# PCB_SCH_Left_Main.net
KiCad netlist of a schematic drawn in EasyEDA Pro
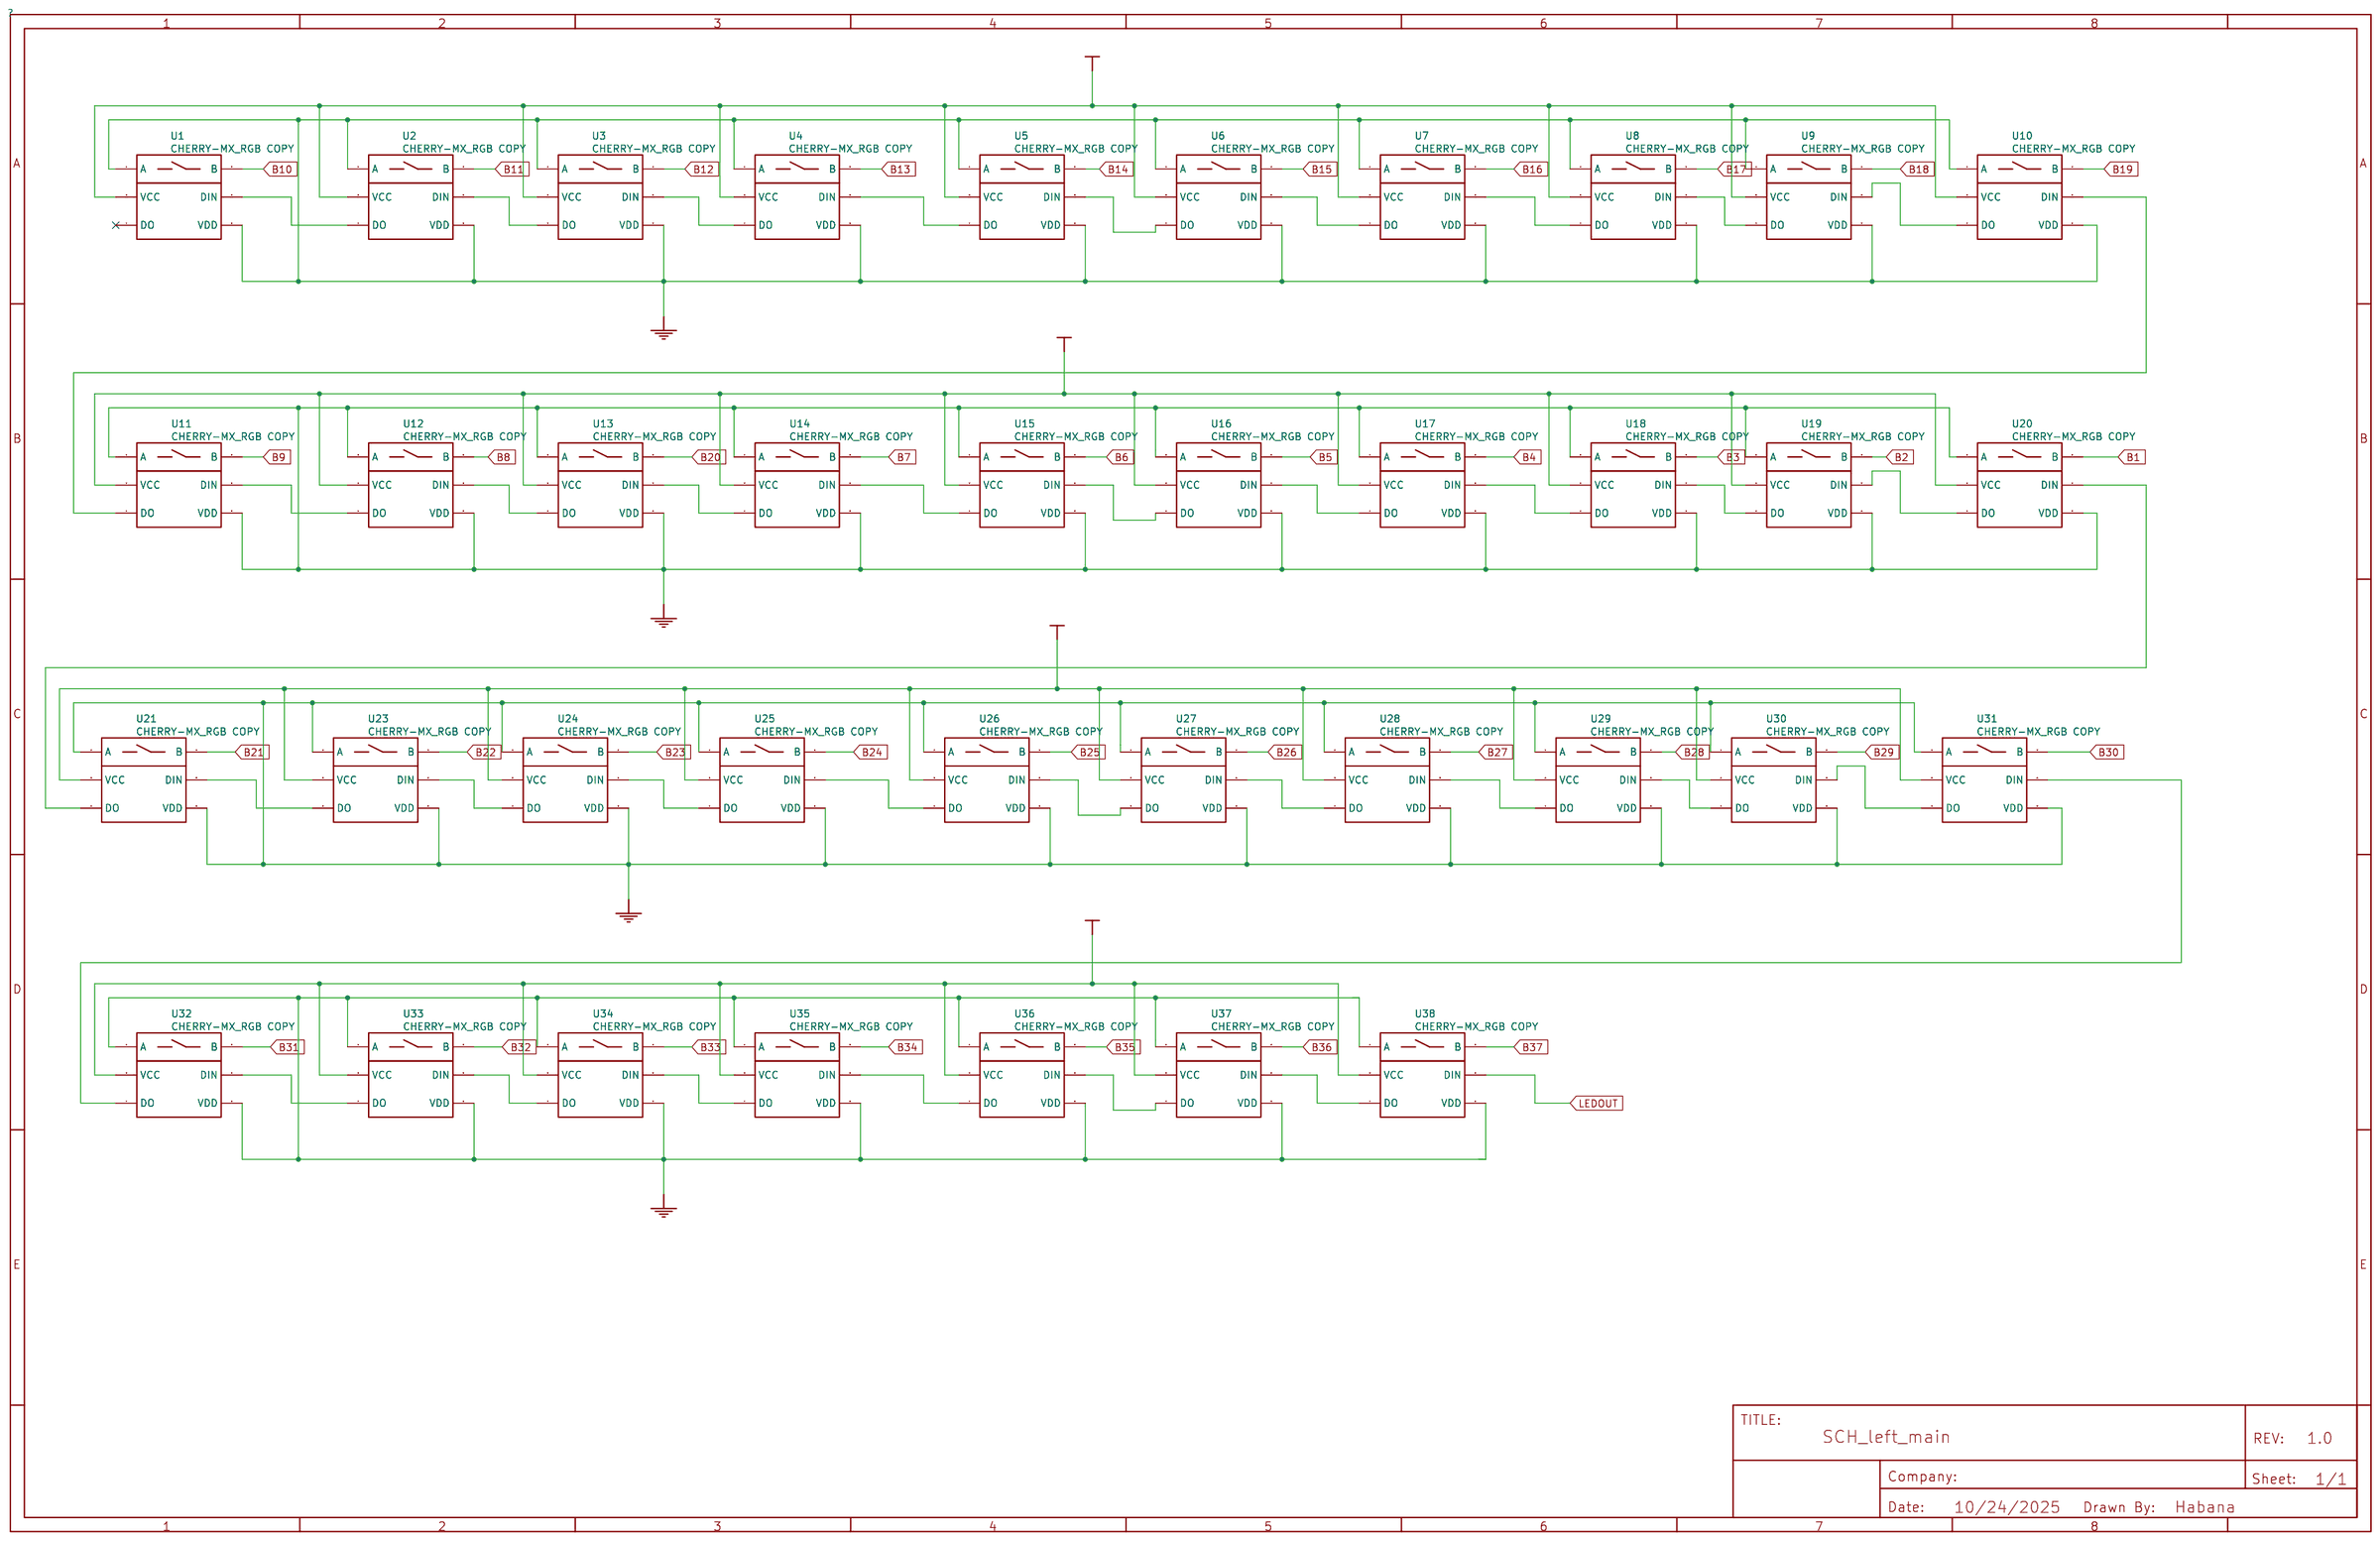
[diagram p0: led and button]
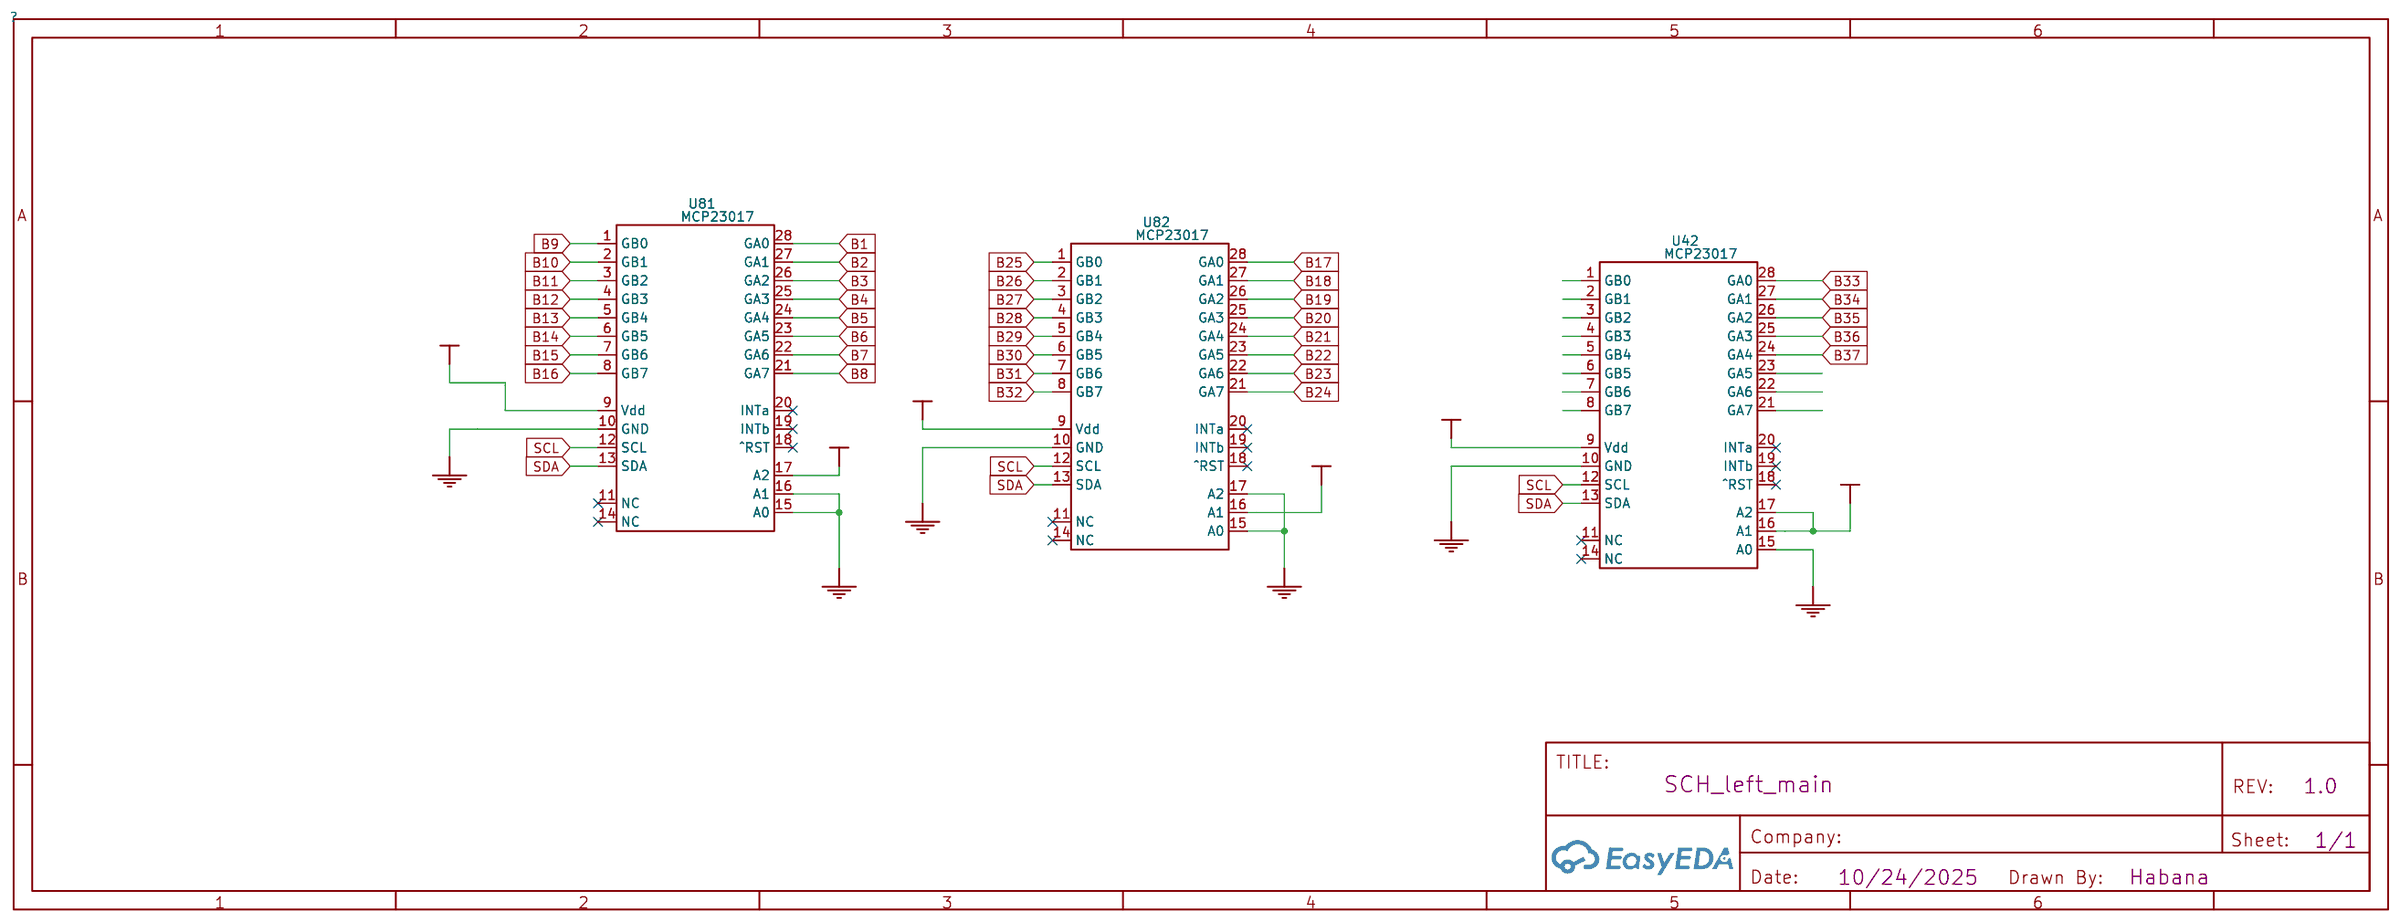
[diagram p1: drivers]
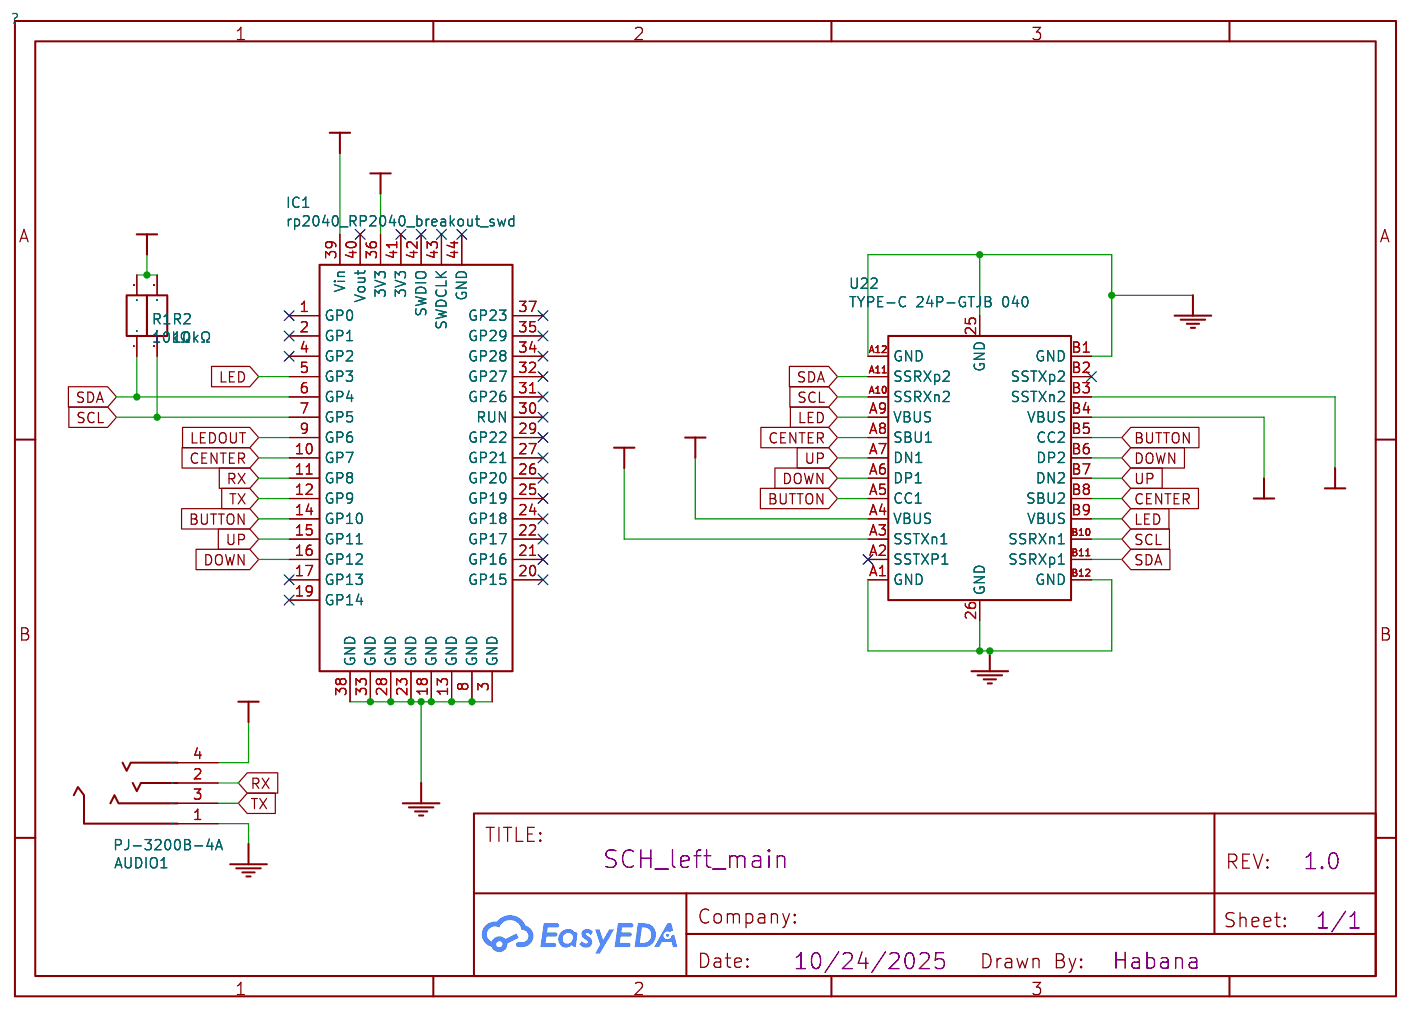
[diagram p2: microcontroller]

(export (version "E")
  (design (tool "Eeschema 10.0.6"))
  (components
    (comp (ref "U1")
      (value "CHERRY-MX_RGB COPY")
      (fields (field (name "Contributor") "unrealin01"))
      (libsource (lib "easyedapro") (part "CHERRY-MX_RGB COPY"))
    )
    (comp (ref "U2")
      (value "CHERRY-MX_RGB COPY")
      (fields (field (name "Contributor") "unrealin01"))
      (libsource (lib "easyedapro") (part "CHERRY-MX_RGB COPY"))
    )
    (comp (ref "U3")
      (value "CHERRY-MX_RGB COPY")
      (fields (field (name "Contributor") "unrealin01"))
      (libsource (lib "easyedapro") (part "CHERRY-MX_RGB COPY"))
    )
    (comp (ref "U4")
      (value "CHERRY-MX_RGB COPY")
      (fields (field (name "Contributor") "unrealin01"))
      (libsource (lib "easyedapro") (part "CHERRY-MX_RGB COPY"))
    )
    (comp (ref "U5")
      (value "CHERRY-MX_RGB COPY")
      (fields (field (name "Contributor") "unrealin01"))
      (libsource (lib "easyedapro") (part "CHERRY-MX_RGB COPY"))
    )
    (comp (ref "U6")
      (value "CHERRY-MX_RGB COPY")
      (fields (field (name "Contributor") "unrealin01"))
      (libsource (lib "easyedapro") (part "CHERRY-MX_RGB COPY"))
    )
    (comp (ref "U7")
      (value "CHERRY-MX_RGB COPY")
      (fields (field (name "Contributor") "unrealin01"))
      (libsource (lib "easyedapro") (part "CHERRY-MX_RGB COPY"))
    )
    (comp (ref "U8")
      (value "CHERRY-MX_RGB COPY")
      (fields (field (name "Contributor") "unrealin01"))
      (libsource (lib "easyedapro") (part "CHERRY-MX_RGB COPY"))
    )
    (comp (ref "U9")
      (value "CHERRY-MX_RGB COPY")
      (fields (field (name "Contributor") "unrealin01"))
      (libsource (lib "easyedapro") (part "CHERRY-MX_RGB COPY"))
    )
    (comp (ref "U10")
      (value "CHERRY-MX_RGB COPY")
      (fields (field (name "Contributor") "unrealin01"))
      (libsource (lib "easyedapro") (part "CHERRY-MX_RGB COPY"))
    )
    (comp (ref "U11")
      (value "CHERRY-MX_RGB COPY")
      (fields (field (name "Contributor") "unrealin01"))
      (libsource (lib "easyedapro") (part "CHERRY-MX_RGB COPY"))
    )
    (comp (ref "U12")
      (value "CHERRY-MX_RGB COPY")
      (fields (field (name "Contributor") "unrealin01"))
      (libsource (lib "easyedapro") (part "CHERRY-MX_RGB COPY"))
    )
    (comp (ref "U13")
      (value "CHERRY-MX_RGB COPY")
      (fields (field (name "Contributor") "unrealin01"))
      (libsource (lib "easyedapro") (part "CHERRY-MX_RGB COPY"))
    )
    (comp (ref "U14")
      (value "CHERRY-MX_RGB COPY")
      (fields (field (name "Contributor") "unrealin01"))
      (libsource (lib "easyedapro") (part "CHERRY-MX_RGB COPY"))
    )
    (comp (ref "U15")
      (value "CHERRY-MX_RGB COPY")
      (fields (field (name "Contributor") "unrealin01"))
      (libsource (lib "easyedapro") (part "CHERRY-MX_RGB COPY"))
    )
    (comp (ref "U16")
      (value "CHERRY-MX_RGB COPY")
      (fields (field (name "Contributor") "unrealin01"))
      (libsource (lib "easyedapro") (part "CHERRY-MX_RGB COPY"))
    )
    (comp (ref "U17")
      (value "CHERRY-MX_RGB COPY")
      (fields (field (name "Contributor") "unrealin01"))
      (libsource (lib "easyedapro") (part "CHERRY-MX_RGB COPY"))
    )
    (comp (ref "U18")
      (value "CHERRY-MX_RGB COPY")
      (fields (field (name "Contributor") "unrealin01"))
      (libsource (lib "easyedapro") (part "CHERRY-MX_RGB COPY"))
    )
    (comp (ref "U19")
      (value "CHERRY-MX_RGB COPY")
      (fields (field (name "Contributor") "unrealin01"))
      (libsource (lib "easyedapro") (part "CHERRY-MX_RGB COPY"))
    )
    (comp (ref "U20")
      (value "CHERRY-MX_RGB COPY")
      (fields (field (name "Contributor") "unrealin01"))
      (libsource (lib "easyedapro") (part "CHERRY-MX_RGB COPY"))
    )
    (comp (ref "U21")
      (value "CHERRY-MX_RGB COPY")
      (fields (field (name "Contributor") "unrealin01"))
      (libsource (lib "easyedapro") (part "CHERRY-MX_RGB COPY"))
    )
    (comp (ref "U23")
      (value "CHERRY-MX_RGB COPY")
      (fields (field (name "Contributor") "unrealin01"))
      (libsource (lib "easyedapro") (part "CHERRY-MX_RGB COPY"))
    )
    (comp (ref "U24")
      (value "CHERRY-MX_RGB COPY")
      (fields (field (name "Contributor") "unrealin01"))
      (libsource (lib "easyedapro") (part "CHERRY-MX_RGB COPY"))
    )
    (comp (ref "U25")
      (value "CHERRY-MX_RGB COPY")
      (fields (field (name "Contributor") "unrealin01"))
      (libsource (lib "easyedapro") (part "CHERRY-MX_RGB COPY"))
    )
    (comp (ref "U26")
      (value "CHERRY-MX_RGB COPY")
      (fields (field (name "Contributor") "unrealin01"))
      (libsource (lib "easyedapro") (part "CHERRY-MX_RGB COPY"))
    )
    (comp (ref "U27")
      (value "CHERRY-MX_RGB COPY")
      (fields (field (name "Contributor") "unrealin01"))
      (libsource (lib "easyedapro") (part "CHERRY-MX_RGB COPY"))
    )
    (comp (ref "U28")
      (value "CHERRY-MX_RGB COPY")
      (fields (field (name "Contributor") "unrealin01"))
      (libsource (lib "easyedapro") (part "CHERRY-MX_RGB COPY"))
    )
    (comp (ref "U29")
      (value "CHERRY-MX_RGB COPY")
      (fields (field (name "Contributor") "unrealin01"))
      (libsource (lib "easyedapro") (part "CHERRY-MX_RGB COPY"))
    )
    (comp (ref "U30")
      (value "CHERRY-MX_RGB COPY")
      (fields (field (name "Contributor") "unrealin01"))
      (libsource (lib "easyedapro") (part "CHERRY-MX_RGB COPY"))
    )
    (comp (ref "U31")
      (value "CHERRY-MX_RGB COPY")
      (fields (field (name "Contributor") "unrealin01"))
      (libsource (lib "easyedapro") (part "CHERRY-MX_RGB COPY"))
    )
    (comp (ref "U32")
      (value "CHERRY-MX_RGB COPY")
      (fields (field (name "Contributor") "unrealin01"))
      (libsource (lib "easyedapro") (part "CHERRY-MX_RGB COPY"))
    )
    (comp (ref "U33")
      (value "CHERRY-MX_RGB COPY")
      (fields (field (name "Contributor") "unrealin01"))
      (libsource (lib "easyedapro") (part "CHERRY-MX_RGB COPY"))
    )
    (comp (ref "U34")
      (value "CHERRY-MX_RGB COPY")
      (fields (field (name "Contributor") "unrealin01"))
      (libsource (lib "easyedapro") (part "CHERRY-MX_RGB COPY"))
    )
    (comp (ref "U35")
      (value "CHERRY-MX_RGB COPY")
      (fields (field (name "Contributor") "unrealin01"))
      (libsource (lib "easyedapro") (part "CHERRY-MX_RGB COPY"))
    )
    (comp (ref "U36")
      (value "CHERRY-MX_RGB COPY")
      (fields (field (name "Contributor") "unrealin01"))
      (libsource (lib "easyedapro") (part "CHERRY-MX_RGB COPY"))
    )
    (comp (ref "U37")
      (value "CHERRY-MX_RGB COPY")
      (fields (field (name "Contributor") "unrealin01"))
      (libsource (lib "easyedapro") (part "CHERRY-MX_RGB COPY"))
    )
    (comp (ref "U38")
      (value "CHERRY-MX_RGB COPY")
      (fields (field (name "Contributor") "unrealin01"))
      (libsource (lib "easyedapro") (part "CHERRY-MX_RGB COPY"))
    )
    (comp (ref "U42")
      (value "MCP23017")
      (fields (field (name "Contributor") "tsvstar"))
      (libsource (lib "easyedapro") (part "MCP23017"))
    )
    (comp (ref "U81")
      (value "MCP23017")
      (fields (field (name "Contributor") "tsvstar"))
      (libsource (lib "easyedapro") (part "MCP23017"))
    )
    (comp (ref "U82")
      (value "MCP23017")
      (fields (field (name "Contributor") "tsvstar"))
      (libsource (lib "easyedapro") (part "MCP23017"))
    )
    (comp (ref "AUDIO1")
      (value "PJ-3200B-4A")
      (footprint "easyedapro:AUDIO-TH_PJ-3200B-4A")
      (fields (field (name "Manufacturer") "韩国韩荣") (field (name "Contributor") "LCSC"))
      (libsource (lib "easyedapro") (part "PJ-3200B-4A"))
    )
    (comp (ref "IC1")
      (value "rp2040_RP2040_breakout_swd")
      (fields (field (name "Contributor") "rataweb"))
      (libsource (lib "easyedapro") (part "rp2040_RP2040_breakout_swd"))
    )
    (comp (ref "R1")
      (value "10kΩ")
      (footprint "easyedapro:R1206")
      (fields
        (field (name "Manufacturer Part") "RCT0610KJLF")
        (field (name "Manufacturer") "HKR(香港电阻)")
        (field (name "Contributor") "LCSC")
      )
      (libsource (lib "easyedapro") (part "10kΩ"))
    )
    (comp (ref "R2")
      (value "10kΩ")
      (footprint "easyedapro:R1206")
      (fields
        (field (name "Manufacturer Part") "RCT0610KJLF")
        (field (name "Manufacturer") "HKR(香港电阻)")
        (field (name "Contributor") "LCSC")
      )
      (libsource (lib "easyedapro") (part "10kΩ"))
    )
    (comp (ref "U22")
      (value "TYPE-C 24P-GTJB 040")
      (footprint "easyedapro:USB-C-SMD_TYPE-C-24P-GTJB-040")
      (fields (field (name "Manufacturer") "SHOU HAN(首韩)") (field (name "Contributor") "lcsc"))
      (libsource (lib "easyedapro") (part "TYPE-C 24P-GTJB 040"))
    )
  )
  (nets
    (net (code "1") (name "+5V") (class "Default")
      (node (ref "IC1") (pin "39") (pinfunction "Vin_39") (pintype "unspecified"))
      (node (ref "R1") (pin "2") (pinfunction "2_2") (pintype "unspecified"))
      (node (ref "R2") (pin "2") (pinfunction "2_2") (pintype "unspecified"))
      (node (ref "U1") (pin "3") (pinfunction "VCC_3") (pintype "unspecified"))
      (node (ref "U10") (pin "3") (pinfunction "VCC_3") (pintype "unspecified"))
      (node (ref "U11") (pin "3") (pinfunction "VCC_3") (pintype "unspecified"))
      (node (ref "U12") (pin "3") (pinfunction "VCC_3") (pintype "unspecified"))
      (node (ref "U13") (pin "3") (pinfunction "VCC_3") (pintype "unspecified"))
      (node (ref "U14") (pin "3") (pinfunction "VCC_3") (pintype "unspecified"))
      (node (ref "U15") (pin "3") (pinfunction "VCC_3") (pintype "unspecified"))
      (node (ref "U16") (pin "3") (pinfunction "VCC_3") (pintype "unspecified"))
      (node (ref "U17") (pin "3") (pinfunction "VCC_3") (pintype "unspecified"))
      (node (ref "U18") (pin "3") (pinfunction "VCC_3") (pintype "unspecified"))
      (node (ref "U19") (pin "3") (pinfunction "VCC_3") (pintype "unspecified"))
      (node (ref "U2") (pin "3") (pinfunction "VCC_3") (pintype "unspecified"))
      (node (ref "U20") (pin "3") (pinfunction "VCC_3") (pintype "unspecified"))
      (node (ref "U21") (pin "3") (pinfunction "VCC_3") (pintype "unspecified"))
      (node (ref "U22") (pin "A4") (pinfunction "VBUS_A4") (pintype "unspecified"))
      (node (ref "U22") (pin "B4") (pinfunction "VBUS_B4") (pintype "unspecified"))
      (node (ref "U23") (pin "3") (pinfunction "VCC_3") (pintype "unspecified"))
      (node (ref "U24") (pin "3") (pinfunction "VCC_3") (pintype "unspecified"))
      (node (ref "U25") (pin "3") (pinfunction "VCC_3") (pintype "unspecified"))
      (node (ref "U26") (pin "3") (pinfunction "VCC_3") (pintype "unspecified"))
      (node (ref "U27") (pin "3") (pinfunction "VCC_3") (pintype "unspecified"))
      (node (ref "U28") (pin "3") (pinfunction "VCC_3") (pintype "unspecified"))
      (node (ref "U29") (pin "3") (pinfunction "VCC_3") (pintype "unspecified"))
      (node (ref "U3") (pin "3") (pinfunction "VCC_3") (pintype "unspecified"))
      (node (ref "U30") (pin "3") (pinfunction "VCC_3") (pintype "unspecified"))
      (node (ref "U31") (pin "3") (pinfunction "VCC_3") (pintype "unspecified"))
      (node (ref "U32") (pin "3") (pinfunction "VCC_3") (pintype "unspecified"))
      (node (ref "U33") (pin "3") (pinfunction "VCC_3") (pintype "unspecified"))
      (node (ref "U34") (pin "3") (pinfunction "VCC_3") (pintype "unspecified"))
      (node (ref "U35") (pin "3") (pinfunction "VCC_3") (pintype "unspecified"))
      (node (ref "U36") (pin "3") (pinfunction "VCC_3") (pintype "unspecified"))
      (node (ref "U37") (pin "3") (pinfunction "VCC_3") (pintype "unspecified"))
      (node (ref "U38") (pin "3") (pinfunction "VCC_3") (pintype "unspecified"))
      (node (ref "U4") (pin "3") (pinfunction "VCC_3") (pintype "unspecified"))
      (node (ref "U5") (pin "3") (pinfunction "VCC_3") (pintype "unspecified"))
      (node (ref "U6") (pin "3") (pinfunction "VCC_3") (pintype "unspecified"))
      (node (ref "U7") (pin "3") (pinfunction "VCC_3") (pintype "unspecified"))
      (node (ref "U8") (pin "3") (pinfunction "VCC_3") (pintype "unspecified"))
      (node (ref "U9") (pin "3") (pinfunction "VCC_3") (pintype "unspecified"))
    )
    (net (code "2") (name "B1") (class "Default")
      (node (ref "U20") (pin "2") (pinfunction "B_2") (pintype "unspecified"))
      (node (ref "U81") (pin "28") (pinfunction "GA0_28") (pintype "unspecified"))
    )
    (net (code "3") (name "B2") (class "Default")
      (node (ref "U19") (pin "2") (pinfunction "B_2") (pintype "unspecified"))
      (node (ref "U81") (pin "27") (pinfunction "GA1_27") (pintype "unspecified"))
    )
    (net (code "4") (name "B3") (class "Default")
      (node (ref "U18") (pin "2") (pinfunction "B_2") (pintype "unspecified"))
      (node (ref "U81") (pin "26") (pinfunction "GA2_26") (pintype "unspecified"))
    )
    (net (code "5") (name "B4") (class "Default")
      (node (ref "U17") (pin "2") (pinfunction "B_2") (pintype "unspecified"))
      (node (ref "U81") (pin "25") (pinfunction "GA3_25") (pintype "unspecified"))
    )
    (net (code "6") (name "B5") (class "Default")
      (node (ref "U16") (pin "2") (pinfunction "B_2") (pintype "unspecified"))
      (node (ref "U81") (pin "24") (pinfunction "GA4_24") (pintype "unspecified"))
    )
    (net (code "7") (name "B6") (class "Default")
      (node (ref "U15") (pin "2") (pinfunction "B_2") (pintype "unspecified"))
      (node (ref "U81") (pin "23") (pinfunction "GA5_23") (pintype "unspecified"))
    )
    (net (code "8") (name "B7") (class "Default")
      (node (ref "U14") (pin "2") (pinfunction "B_2") (pintype "unspecified"))
      (node (ref "U81") (pin "22") (pinfunction "GA6_22") (pintype "unspecified"))
    )
    (net (code "9") (name "B8") (class "Default")
      (node (ref "U12") (pin "2") (pinfunction "B_2") (pintype "unspecified"))
      (node (ref "U81") (pin "21") (pinfunction "GA7_21") (pintype "unspecified"))
    )
    (net (code "10") (name "B9") (class "Default")
      (node (ref "U11") (pin "2") (pinfunction "B_2") (pintype "unspecified"))
      (node (ref "U81") (pin "1") (pinfunction "GB0_1") (pintype "unspecified"))
    )
    (net (code "11") (name "B10") (class "Default")
      (node (ref "U1") (pin "2") (pinfunction "B_2") (pintype "unspecified"))
      (node (ref "U81") (pin "2") (pinfunction "GB1_2") (pintype "unspecified"))
    )
    (net (code "12") (name "B11") (class "Default")
      (node (ref "U2") (pin "2") (pinfunction "B_2") (pintype "unspecified"))
      (node (ref "U81") (pin "3") (pinfunction "GB2_3") (pintype "unspecified"))
    )
    (net (code "13") (name "B12") (class "Default")
      (node (ref "U3") (pin "2") (pinfunction "B_2") (pintype "unspecified"))
      (node (ref "U81") (pin "4") (pinfunction "GB3_4") (pintype "unspecified"))
    )
    (net (code "14") (name "B13") (class "Default")
      (node (ref "U4") (pin "2") (pinfunction "B_2") (pintype "unspecified"))
      (node (ref "U81") (pin "5") (pinfunction "GB4_5") (pintype "unspecified"))
    )
    (net (code "15") (name "B14") (class "Default")
      (node (ref "U5") (pin "2") (pinfunction "B_2") (pintype "unspecified"))
      (node (ref "U81") (pin "6") (pinfunction "GB5_6") (pintype "unspecified"))
    )
    (net (code "16") (name "B15") (class "Default")
      (node (ref "U6") (pin "2") (pinfunction "B_2") (pintype "unspecified"))
      (node (ref "U81") (pin "7") (pinfunction "GB6_7") (pintype "unspecified"))
    )
    (net (code "17") (name "B16") (class "Default")
      (node (ref "U7") (pin "2") (pinfunction "B_2") (pintype "unspecified"))
      (node (ref "U81") (pin "8") (pinfunction "GB7_8") (pintype "unspecified"))
    )
    (net (code "18") (name "B17") (class "Default")
      (node (ref "U8") (pin "2") (pinfunction "B_2") (pintype "unspecified"))
      (node (ref "U82") (pin "28") (pinfunction "GA0_28") (pintype "unspecified"))
    )
    (net (code "19") (name "B18") (class "Default")
      (node (ref "U82") (pin "27") (pinfunction "GA1_27") (pintype "unspecified"))
      (node (ref "U9") (pin "2") (pinfunction "B_2") (pintype "unspecified"))
    )
    (net (code "20") (name "B19") (class "Default")
      (node (ref "U10") (pin "2") (pinfunction "B_2") (pintype "unspecified"))
      (node (ref "U82") (pin "26") (pinfunction "GA2_26") (pintype "unspecified"))
    )
    (net (code "21") (name "B20") (class "Default")
      (node (ref "U13") (pin "2") (pinfunction "B_2") (pintype "unspecified"))
      (node (ref "U82") (pin "25") (pinfunction "GA3_25") (pintype "unspecified"))
    )
    (net (code "22") (name "B21") (class "Default")
      (node (ref "U21") (pin "2") (pinfunction "B_2") (pintype "unspecified"))
      (node (ref "U82") (pin "24") (pinfunction "GA4_24") (pintype "unspecified"))
    )
    (net (code "23") (name "B22") (class "Default")
      (node (ref "U23") (pin "2") (pinfunction "B_2") (pintype "unspecified"))
      (node (ref "U82") (pin "23") (pinfunction "GA5_23") (pintype "unspecified"))
    )
    (net (code "24") (name "B23") (class "Default")
      (node (ref "U24") (pin "2") (pinfunction "B_2") (pintype "unspecified"))
      (node (ref "U82") (pin "22") (pinfunction "GA6_22") (pintype "unspecified"))
    )
    (net (code "25") (name "B24") (class "Default")
      (node (ref "U25") (pin "2") (pinfunction "B_2") (pintype "unspecified"))
      (node (ref "U82") (pin "21") (pinfunction "GA7_21") (pintype "unspecified"))
    )
    (net (code "26") (name "B25") (class "Default")
      (node (ref "U26") (pin "2") (pinfunction "B_2") (pintype "unspecified"))
      (node (ref "U82") (pin "1") (pinfunction "GB0_1") (pintype "unspecified"))
    )
    (net (code "27") (name "B26") (class "Default")
      (node (ref "U27") (pin "2") (pinfunction "B_2") (pintype "unspecified"))
      (node (ref "U82") (pin "2") (pinfunction "GB1_2") (pintype "unspecified"))
    )
    (net (code "28") (name "B27") (class "Default")
      (node (ref "U28") (pin "2") (pinfunction "B_2") (pintype "unspecified"))
      (node (ref "U82") (pin "3") (pinfunction "GB2_3") (pintype "unspecified"))
    )
    (net (code "29") (name "B28") (class "Default")
      (node (ref "U29") (pin "2") (pinfunction "B_2") (pintype "unspecified"))
      (node (ref "U82") (pin "4") (pinfunction "GB3_4") (pintype "unspecified"))
    )
    (net (code "30") (name "B29") (class "Default")
      (node (ref "U30") (pin "2") (pinfunction "B_2") (pintype "unspecified"))
      (node (ref "U82") (pin "5") (pinfunction "GB4_5") (pintype "unspecified"))
    )
    (net (code "31") (name "B30") (class "Default")
      (node (ref "U31") (pin "2") (pinfunction "B_2") (pintype "unspecified"))
      (node (ref "U82") (pin "6") (pinfunction "GB5_6") (pintype "unspecified"))
    )
    (net (code "32") (name "B31") (class "Default")
      (node (ref "U32") (pin "2") (pinfunction "B_2") (pintype "unspecified"))
      (node (ref "U82") (pin "7") (pinfunction "GB6_7") (pintype "unspecified"))
    )
    (net (code "33") (name "B32") (class "Default")
      (node (ref "U33") (pin "2") (pinfunction "B_2") (pintype "unspecified"))
      (node (ref "U82") (pin "8") (pinfunction "GB7_8") (pintype "unspecified"))
    )
    (net (code "34") (name "B33") (class "Default")
      (node (ref "U34") (pin "2") (pinfunction "B_2") (pintype "unspecified"))
      (node (ref "U42") (pin "28") (pinfunction "GA0_28") (pintype "unspecified"))
    )
    (net (code "35") (name "B34") (class "Default")
      (node (ref "U35") (pin "2") (pinfunction "B_2") (pintype "unspecified"))
      (node (ref "U42") (pin "27") (pinfunction "GA1_27") (pintype "unspecified"))
    )
    (net (code "36") (name "B35") (class "Default")
      (node (ref "U36") (pin "2") (pinfunction "B_2") (pintype "unspecified"))
      (node (ref "U42") (pin "26") (pinfunction "GA2_26") (pintype "unspecified"))
    )
    (net (code "37") (name "B36") (class "Default")
      (node (ref "U37") (pin "2") (pinfunction "B_2") (pintype "unspecified"))
      (node (ref "U42") (pin "25") (pinfunction "GA3_25") (pintype "unspecified"))
    )
    (net (code "38") (name "B37") (class "Default")
      (node (ref "U38") (pin "2") (pinfunction "B_2") (pintype "unspecified"))
      (node (ref "U42") (pin "24") (pinfunction "GA4_24") (pintype "unspecified"))
    )
    (net (code "39") (name "BUTTON") (class "Default")
      (node (ref "IC1") (pin "14") (pinfunction "GP10_14") (pintype "unspecified"))
      (node (ref "U22") (pin "A5") (pinfunction "CC1_A5") (pintype "unspecified"))
      (node (ref "U22") (pin "B5") (pinfunction "CC2_B5") (pintype "unspecified"))
    )
    (net (code "40") (name "CENTER") (class "Default")
      (node (ref "IC1") (pin "10") (pinfunction "GP7_10") (pintype "unspecified"))
      (node (ref "U22") (pin "A8") (pinfunction "SBU1_A8") (pintype "unspecified"))
      (node (ref "U22") (pin "B8") (pinfunction "SBU2_B8") (pintype "unspecified"))
    )
    (net (code "41") (name "DOWN") (class "Default")
      (node (ref "IC1") (pin "16") (pinfunction "GP12_16") (pintype "unspecified"))
      (node (ref "U22") (pin "A6") (pinfunction "DP1_A6") (pintype "unspecified"))
      (node (ref "U22") (pin "B6") (pinfunction "DP2_B6") (pintype "unspecified"))
    )
    (net (code "42") (name "GND") (class "Default")
      (node (ref "AUDIO1") (pin "1") (pinfunction "1_1") (pintype "unspecified"))
      (node (ref "IC1") (pin "13") (pinfunction "GND_13") (pintype "unspecified"))
      (node (ref "IC1") (pin "18") (pinfunction "GND_18") (pintype "unspecified"))
      (node (ref "IC1") (pin "23") (pinfunction "GND_23") (pintype "unspecified"))
      (node (ref "IC1") (pin "28") (pinfunction "GND_28") (pintype "unspecified"))
      (node (ref "IC1") (pin "3") (pinfunction "GND_3") (pintype "unspecified"))
      (node (ref "IC1") (pin "33") (pinfunction "GND_33") (pintype "unspecified"))
      (node (ref "IC1") (pin "38") (pinfunction "GND_38") (pintype "unspecified"))
      (node (ref "IC1") (pin "8") (pinfunction "GND_8") (pintype "unspecified"))
      (node (ref "U1") (pin "1") (pinfunction "A_1") (pintype "unspecified"))
      (node (ref "U1") (pin "5") (pinfunction "VDD_5") (pintype "unspecified"))
      (node (ref "U10") (pin "1") (pinfunction "A_1") (pintype "unspecified"))
      (node (ref "U10") (pin "5") (pinfunction "VDD_5") (pintype "unspecified"))
      (node (ref "U11") (pin "1") (pinfunction "A_1") (pintype "unspecified"))
      (node (ref "U11") (pin "5") (pinfunction "VDD_5") (pintype "unspecified"))
      (node (ref "U12") (pin "1") (pinfunction "A_1") (pintype "unspecified"))
      (node (ref "U12") (pin "5") (pinfunction "VDD_5") (pintype "unspecified"))
      (node (ref "U13") (pin "1") (pinfunction "A_1") (pintype "unspecified"))
      (node (ref "U13") (pin "5") (pinfunction "VDD_5") (pintype "unspecified"))
      (node (ref "U14") (pin "1") (pinfunction "A_1") (pintype "unspecified"))
      (node (ref "U14") (pin "5") (pinfunction "VDD_5") (pintype "unspecified"))
      (node (ref "U15") (pin "1") (pinfunction "A_1") (pintype "unspecified"))
      (node (ref "U15") (pin "5") (pinfunction "VDD_5") (pintype "unspecified"))
      (node (ref "U16") (pin "1") (pinfunction "A_1") (pintype "unspecified"))
      (node (ref "U16") (pin "5") (pinfunction "VDD_5") (pintype "unspecified"))
      (node (ref "U17") (pin "1") (pinfunction "A_1") (pintype "unspecified"))
      (node (ref "U17") (pin "5") (pinfunction "VDD_5") (pintype "unspecified"))
      (node (ref "U18") (pin "1") (pinfunction "A_1") (pintype "unspecified"))
      (node (ref "U18") (pin "5") (pinfunction "VDD_5") (pintype "unspecified"))
      (node (ref "U19") (pin "1") (pinfunction "A_1") (pintype "unspecified"))
      (node (ref "U19") (pin "5") (pinfunction "VDD_5") (pintype "unspecified"))
      (node (ref "U2") (pin "1") (pinfunction "A_1") (pintype "unspecified"))
      (node (ref "U2") (pin "5") (pinfunction "VDD_5") (pintype "unspecified"))
      (node (ref "U20") (pin "1") (pinfunction "A_1") (pintype "unspecified"))
      (node (ref "U20") (pin "5") (pinfunction "VDD_5") (pintype "unspecified"))
      (node (ref "U21") (pin "1") (pinfunction "A_1") (pintype "unspecified"))
      (node (ref "U21") (pin "5") (pinfunction "VDD_5") (pintype "unspecified"))
      (node (ref "U22") (pin "25") (pinfunction "GND_25") (pintype "unspecified"))
      (node (ref "U22") (pin "26") (pinfunction "GND_26") (pintype "unspecified"))
      (node (ref "U22") (pin "A1") (pinfunction "GND_A1") (pintype "unspecified"))
      (node (ref "U22") (pin "A12") (pinfunction "GND_A12") (pintype "unspecified"))
      (node (ref "U22") (pin "B1") (pinfunction "GND_B1") (pintype "unspecified"))
      (node (ref "U22") (pin "B12") (pinfunction "GND_B12") (pintype "unspecified"))
      (node (ref "U23") (pin "1") (pinfunction "A_1") (pintype "unspecified"))
      (node (ref "U23") (pin "5") (pinfunction "VDD_5") (pintype "unspecified"))
      (node (ref "U24") (pin "1") (pinfunction "A_1") (pintype "unspecified"))
      (node (ref "U24") (pin "5") (pinfunction "VDD_5") (pintype "unspecified"))
      (node (ref "U25") (pin "1") (pinfunction "A_1") (pintype "unspecified"))
      (node (ref "U25") (pin "5") (pinfunction "VDD_5") (pintype "unspecified"))
      (node (ref "U26") (pin "1") (pinfunction "A_1") (pintype "unspecified"))
      (node (ref "U26") (pin "5") (pinfunction "VDD_5") (pintype "unspecified"))
      (node (ref "U27") (pin "1") (pinfunction "A_1") (pintype "unspecified"))
      (node (ref "U27") (pin "5") (pinfunction "VDD_5") (pintype "unspecified"))
      (node (ref "U28") (pin "1") (pinfunction "A_1") (pintype "unspecified"))
      (node (ref "U28") (pin "5") (pinfunction "VDD_5") (pintype "unspecified"))
      (node (ref "U29") (pin "1") (pinfunction "A_1") (pintype "unspecified"))
      (node (ref "U29") (pin "5") (pinfunction "VDD_5") (pintype "unspecified"))
      (node (ref "U3") (pin "1") (pinfunction "A_1") (pintype "unspecified"))
      (node (ref "U3") (pin "5") (pinfunction "VDD_5") (pintype "unspecified"))
      (node (ref "U30") (pin "1") (pinfunction "A_1") (pintype "unspecified"))
      (node (ref "U30") (pin "5") (pinfunction "VDD_5") (pintype "unspecified"))
      (node (ref "U31") (pin "1") (pinfunction "A_1") (pintype "unspecified"))
      (node (ref "U31") (pin "5") (pinfunction "VDD_5") (pintype "unspecified"))
      (node (ref "U32") (pin "1") (pinfunction "A_1") (pintype "unspecified"))
      (node (ref "U32") (pin "5") (pinfunction "VDD_5") (pintype "unspecified"))
      (node (ref "U33") (pin "1") (pinfunction "A_1") (pintype "unspecified"))
      (node (ref "U33") (pin "5") (pinfunction "VDD_5") (pintype "unspecified"))
      (node (ref "U34") (pin "1") (pinfunction "A_1") (pintype "unspecified"))
      (node (ref "U34") (pin "5") (pinfunction "VDD_5") (pintype "unspecified"))
      (node (ref "U35") (pin "1") (pinfunction "A_1") (pintype "unspecified"))
      (node (ref "U35") (pin "5") (pinfunction "VDD_5") (pintype "unspecified"))
      (node (ref "U36") (pin "1") (pinfunction "A_1") (pintype "unspecified"))
      (node (ref "U36") (pin "5") (pinfunction "VDD_5") (pintype "unspecified"))
      (node (ref "U37") (pin "1") (pinfunction "A_1") (pintype "unspecified"))
      (node (ref "U37") (pin "5") (pinfunction "VDD_5") (pintype "unspecified"))
      (node (ref "U38") (pin "1") (pinfunction "A_1") (pintype "unspecified"))
      (node (ref "U38") (pin "5") (pinfunction "VDD_5") (pintype "unspecified"))
      (node (ref "U4") (pin "1") (pinfunction "A_1") (pintype "unspecified"))
      (node (ref "U4") (pin "5") (pinfunction "VDD_5") (pintype "unspecified"))
      (node (ref "U42") (pin "10") (pinfunction "GND_10") (pintype "unspecified"))
      (node (ref "U42") (pin "15") (pinfunction "A0_15") (pintype "unspecified"))
      (node (ref "U5") (pin "1") (pinfunction "A_1") (pintype "unspecified"))
      (node (ref "U5") (pin "5") (pinfunction "VDD_5") (pintype "unspecified"))
      (node (ref "U6") (pin "1") (pinfunction "A_1") (pintype "unspecified"))
      (node (ref "U6") (pin "5") (pinfunction "VDD_5") (pintype "unspecified"))
      (node (ref "U7") (pin "1") (pinfunction "A_1") (pintype "unspecified"))
      (node (ref "U7") (pin "5") (pinfunction "VDD_5") (pintype "unspecified"))
      (node (ref "U8") (pin "1") (pinfunction "A_1") (pintype "unspecified"))
      (node (ref "U8") (pin "5") (pinfunction "VDD_5") (pintype "unspecified"))
      (node (ref "U81") (pin "10") (pinfunction "GND_10") (pintype "unspecified"))
      (node (ref "U81") (pin "15") (pinfunction "A0_15") (pintype "unspecified"))
      (node (ref "U81") (pin "16") (pinfunction "A1_16") (pintype "unspecified"))
      (node (ref "U82") (pin "10") (pinfunction "GND_10") (pintype "unspecified"))
      (node (ref "U82") (pin "15") (pinfunction "A0_15") (pintype "unspecified"))
      (node (ref "U82") (pin "17") (pinfunction "A2_17") (pintype "unspecified"))
      (node (ref "U9") (pin "1") (pinfunction "A_1") (pintype "unspecified"))
      (node (ref "U9") (pin "5") (pinfunction "VDD_5") (pintype "unspecified"))
    )
    (net (code "43") (name "LED") (class "Default")
      (node (ref "IC1") (pin "5") (pinfunction "GP3_5") (pintype "unspecified"))
      (node (ref "U22") (pin "A9") (pinfunction "VBUS_A9") (pintype "unspecified"))
      (node (ref "U22") (pin "B9") (pinfunction "VBUS_B9") (pintype "unspecified"))
    )
    (net (code "44") (name "LEDOUT") (class "Default")
      (node (ref "IC1") (pin "9") (pinfunction "GP6_9") (pintype "unspecified"))
      (node (ref "U38") (pin "6") (pinfunction "DIN_6") (pintype "unspecified"))
    )
    (net (code "45") (name "Net-(U1-DIN)") (class "Default")
      (node (ref "U1") (pin "6") (pinfunction "DIN_6") (pintype "unspecified"))
      (node (ref "U2") (pin "4") (pinfunction "DO_4") (pintype "unspecified"))
    )
    (net (code "46") (name "Net-(U2-DIN)") (class "Default")
      (node (ref "U2") (pin "6") (pinfunction "DIN_6") (pintype "unspecified"))
      (node (ref "U3") (pin "4") (pinfunction "DO_4") (pintype "unspecified"))
    )
    (net (code "47") (name "Net-(U3-DIN)") (class "Default")
      (node (ref "U3") (pin "6") (pinfunction "DIN_6") (pintype "unspecified"))
      (node (ref "U4") (pin "4") (pinfunction "DO_4") (pintype "unspecified"))
    )
    (net (code "48") (name "Net-(U4-DIN)") (class "Default")
      (node (ref "U4") (pin "6") (pinfunction "DIN_6") (pintype "unspecified"))
      (node (ref "U5") (pin "4") (pinfunction "DO_4") (pintype "unspecified"))
    )
    (net (code "49") (name "Net-(U5-DIN)") (class "Default")
      (node (ref "U5") (pin "6") (pinfunction "DIN_6") (pintype "unspecified"))
      (node (ref "U6") (pin "4") (pinfunction "DO_4") (pintype "unspecified"))
    )
    (net (code "50") (name "Net-(U6-DIN)") (class "Default")
      (node (ref "U6") (pin "6") (pinfunction "DIN_6") (pintype "unspecified"))
      (node (ref "U7") (pin "4") (pinfunction "DO_4") (pintype "unspecified"))
    )
    (net (code "51") (name "Net-(U7-DIN)") (class "Default")
      (node (ref "U7") (pin "6") (pinfunction "DIN_6") (pintype "unspecified"))
      (node (ref "U8") (pin "4") (pinfunction "DO_4") (pintype "unspecified"))
    )
    (net (code "52") (name "Net-(U8-DIN)") (class "Default")
      (node (ref "U8") (pin "6") (pinfunction "DIN_6") (pintype "unspecified"))
      (node (ref "U9") (pin "4") (pinfunction "DO_4") (pintype "unspecified"))
    )
    (net (code "53") (name "Net-(U10-DIN)") (class "Default")
      (node (ref "U10") (pin "6") (pinfunction "DIN_6") (pintype "unspecified"))
      (node (ref "U11") (pin "4") (pinfunction "DO_4") (pintype "unspecified"))
    )
    (net (code "54") (name "Net-(U10-DO)") (class "Default")
      (node (ref "U10") (pin "4") (pinfunction "DO_4") (pintype "unspecified"))
      (node (ref "U9") (pin "6") (pinfunction "DIN_6") (pintype "unspecified"))
    )
    (net (code "55") (name "Net-(U11-DIN)") (class "Default")
      (node (ref "U11") (pin "6") (pinfunction "DIN_6") (pintype "unspecified"))
      (node (ref "U12") (pin "4") (pinfunction "DO_4") (pintype "unspecified"))
    )
    (net (code "56") (name "Net-(U12-DIN)") (class "Default")
      (node (ref "U12") (pin "6") (pinfunction "DIN_6") (pintype "unspecified"))
      (node (ref "U13") (pin "4") (pinfunction "DO_4") (pintype "unspecified"))
    )
    (net (code "57") (name "Net-(U13-DIN)") (class "Default")
      (node (ref "U13") (pin "6") (pinfunction "DIN_6") (pintype "unspecified"))
      (node (ref "U14") (pin "4") (pinfunction "DO_4") (pintype "unspecified"))
    )
    (net (code "58") (name "Net-(U14-DIN)") (class "Default")
      (node (ref "U14") (pin "6") (pinfunction "DIN_6") (pintype "unspecified"))
      (node (ref "U15") (pin "4") (pinfunction "DO_4") (pintype "unspecified"))
    )
    (net (code "59") (name "Net-(U15-DIN)") (class "Default")
      (node (ref "U15") (pin "6") (pinfunction "DIN_6") (pintype "unspecified"))
      (node (ref "U16") (pin "4") (pinfunction "DO_4") (pintype "unspecified"))
    )
    (net (code "60") (name "Net-(U16-DIN)") (class "Default")
      (node (ref "U16") (pin "6") (pinfunction "DIN_6") (pintype "unspecified"))
      (node (ref "U17") (pin "4") (pinfunction "DO_4") (pintype "unspecified"))
    )
    (net (code "61") (name "Net-(U17-DIN)") (class "Default")
      (node (ref "U17") (pin "6") (pinfunction "DIN_6") (pintype "unspecified"))
      (node (ref "U18") (pin "4") (pinfunction "DO_4") (pintype "unspecified"))
    )
    (net (code "62") (name "Net-(U18-DIN)") (class "Default")
      (node (ref "U18") (pin "6") (pinfunction "DIN_6") (pintype "unspecified"))
      (node (ref "U19") (pin "4") (pinfunction "DO_4") (pintype "unspecified"))
    )
    (net (code "63") (name "Net-(U19-DIN)") (class "Default")
      (node (ref "U19") (pin "6") (pinfunction "DIN_6") (pintype "unspecified"))
      (node (ref "U20") (pin "4") (pinfunction "DO_4") (pintype "unspecified"))
    )
    (net (code "64") (name "Net-(U20-DIN)") (class "Default")
      (node (ref "U20") (pin "6") (pinfunction "DIN_6") (pintype "unspecified"))
      (node (ref "U21") (pin "4") (pinfunction "DO_4") (pintype "unspecified"))
    )
    (net (code "65") (name "Net-(U21-DIN)") (class "Default")
      (node (ref "U21") (pin "6") (pinfunction "DIN_6") (pintype "unspecified"))
      (node (ref "U23") (pin "4") (pinfunction "DO_4") (pintype "unspecified"))
    )
    (net (code "66") (name "Net-(U23-DIN)") (class "Default")
      (node (ref "U23") (pin "6") (pinfunction "DIN_6") (pintype "unspecified"))
      (node (ref "U24") (pin "4") (pinfunction "DO_4") (pintype "unspecified"))
    )
    (net (code "67") (name "Net-(U24-DIN)") (class "Default")
      (node (ref "U24") (pin "6") (pinfunction "DIN_6") (pintype "unspecified"))
      (node (ref "U25") (pin "4") (pinfunction "DO_4") (pintype "unspecified"))
    )
    (net (code "68") (name "Net-(U25-DIN)") (class "Default")
      (node (ref "U25") (pin "6") (pinfunction "DIN_6") (pintype "unspecified"))
      (node (ref "U26") (pin "4") (pinfunction "DO_4") (pintype "unspecified"))
    )
    (net (code "69") (name "Net-(U26-DIN)") (class "Default")
      (node (ref "U26") (pin "6") (pinfunction "DIN_6") (pintype "unspecified"))
      (node (ref "U27") (pin "4") (pinfunction "DO_4") (pintype "unspecified"))
    )
    (net (code "70") (name "Net-(U27-DIN)") (class "Default")
      (node (ref "U27") (pin "6") (pinfunction "DIN_6") (pintype "unspecified"))
      (node (ref "U28") (pin "4") (pinfunction "DO_4") (pintype "unspecified"))
    )
    (net (code "71") (name "Net-(U28-DIN)") (class "Default")
      (node (ref "U28") (pin "6") (pinfunction "DIN_6") (pintype "unspecified"))
      (node (ref "U29") (pin "4") (pinfunction "DO_4") (pintype "unspecified"))
    )
    (net (code "72") (name "Net-(U29-DIN)") (class "Default")
      (node (ref "U29") (pin "6") (pinfunction "DIN_6") (pintype "unspecified"))
      (node (ref "U30") (pin "4") (pinfunction "DO_4") (pintype "unspecified"))
    )
    (net (code "73") (name "Net-(U30-DIN)") (class "Default")
      (node (ref "U30") (pin "6") (pinfunction "DIN_6") (pintype "unspecified"))
      (node (ref "U31") (pin "4") (pinfunction "DO_4") (pintype "unspecified"))
    )
    (net (code "74") (name "Net-(U31-DIN)") (class "Default")
      (node (ref "U31") (pin "6") (pinfunction "DIN_6") (pintype "unspecified"))
      (node (ref "U32") (pin "4") (pinfunction "DO_4") (pintype "unspecified"))
    )
    (net (code "75") (name "Net-(U32-DIN)") (class "Default")
      (node (ref "U32") (pin "6") (pinfunction "DIN_6") (pintype "unspecified"))
      (node (ref "U33") (pin "4") (pinfunction "DO_4") (pintype "unspecified"))
    )
    (net (code "76") (name "Net-(U33-DIN)") (class "Default")
      (node (ref "U33") (pin "6") (pinfunction "DIN_6") (pintype "unspecified"))
      (node (ref "U34") (pin "4") (pinfunction "DO_4") (pintype "unspecified"))
    )
    (net (code "77") (name "Net-(U34-DIN)") (class "Default")
      (node (ref "U34") (pin "6") (pinfunction "DIN_6") (pintype "unspecified"))
      (node (ref "U35") (pin "4") (pinfunction "DO_4") (pintype "unspecified"))
    )
    (net (code "78") (name "Net-(U35-DIN)") (class "Default")
      (node (ref "U35") (pin "6") (pinfunction "DIN_6") (pintype "unspecified"))
      (node (ref "U36") (pin "4") (pinfunction "DO_4") (pintype "unspecified"))
    )
    (net (code "79") (name "Net-(U36-DIN)") (class "Default")
      (node (ref "U36") (pin "6") (pinfunction "DIN_6") (pintype "unspecified"))
      (node (ref "U37") (pin "4") (pinfunction "DO_4") (pintype "unspecified"))
    )
    (net (code "80") (name "Net-(U37-DIN)") (class "Default")
      (node (ref "U37") (pin "6") (pinfunction "DIN_6") (pintype "unspecified"))
      (node (ref "U38") (pin "4") (pinfunction "DO_4") (pintype "unspecified"))
    )
    (net (code "81") (name "RX") (class "Default")
      (node (ref "AUDIO1") (pin "2") (pinfunction "2_2") (pintype "unspecified"))
      (node (ref "IC1") (pin "11") (pinfunction "GP8_11") (pintype "unspecified"))
    )
    (net (code "82") (name "SCL") (class "Default")
      (node (ref "IC1") (pin "7") (pinfunction "GP5_7") (pintype "unspecified"))
      (node (ref "R2") (pin "1") (pinfunction "1_1") (pintype "unspecified"))
      (node (ref "U22") (pin "A10") (pinfunction "SSRXn2_A10") (pintype "unspecified"))
      (node (ref "U22") (pin "B10") (pinfunction "SSRXn1_B10") (pintype "unspecified"))
      (node (ref "U42") (pin "12") (pinfunction "SCL_12") (pintype "unspecified"))
      (node (ref "U81") (pin "12") (pinfunction "SCL_12") (pintype "unspecified"))
      (node (ref "U82") (pin "12") (pinfunction "SCL_12") (pintype "unspecified"))
    )
    (net (code "83") (name "SDA") (class "Default")
      (node (ref "IC1") (pin "6") (pinfunction "GP4_6") (pintype "unspecified"))
      (node (ref "R1") (pin "1") (pinfunction "1_1") (pintype "unspecified"))
      (node (ref "U22") (pin "A11") (pinfunction "SSRXp2_A11") (pintype "unspecified"))
      (node (ref "U22") (pin "B11") (pinfunction "SSRXp1_B11") (pintype "unspecified"))
      (node (ref "U42") (pin "13") (pinfunction "SDA_13") (pintype "unspecified"))
      (node (ref "U81") (pin "13") (pinfunction "SDA_13") (pintype "unspecified"))
      (node (ref "U82") (pin "13") (pinfunction "SDA_13") (pintype "unspecified"))
    )
    (net (code "84") (name "TX") (class "Default")
      (node (ref "AUDIO1") (pin "3") (pinfunction "3_3") (pintype "unspecified"))
      (node (ref "IC1") (pin "12") (pinfunction "GP9_12") (pintype "unspecified"))
    )
    (net (code "85") (name "UP") (class "Default")
      (node (ref "IC1") (pin "15") (pinfunction "GP11_15") (pintype "unspecified"))
      (node (ref "U22") (pin "A7") (pinfunction "DN1_A7") (pintype "unspecified"))
      (node (ref "U22") (pin "B7") (pinfunction "DN2_B7") (pintype "unspecified"))
    )
    (net (code "86") (name "VCC") (class "Default")
      (node (ref "AUDIO1") (pin "4") (pinfunction "4_4") (pintype "unspecified"))
      (node (ref "IC1") (pin "36") (pinfunction "3V3_36") (pintype "unspecified"))
      (node (ref "U22") (pin "A3") (pinfunction "SSTXn1_A3") (pintype "unspecified"))
      (node (ref "U22") (pin "B3") (pinfunction "SSTXn2_B3") (pintype "unspecified"))
      (node (ref "U42") (pin "16") (pinfunction "A1_16") (pintype "unspecified"))
      (node (ref "U42") (pin "17") (pinfunction "A2_17") (pintype "unspecified"))
      (node (ref "U42") (pin "9") (pinfunction "Vdd_9") (pintype "unspecified"))
      (node (ref "U81") (pin "17") (pinfunction "A2_17") (pintype "unspecified"))
      (node (ref "U81") (pin "9") (pinfunction "Vdd_9") (pintype "unspecified"))
      (node (ref "U82") (pin "16") (pinfunction "A1_16") (pintype "unspecified"))
      (node (ref "U82") (pin "9") (pinfunction "Vdd_9") (pintype "unspecified"))
    )
    (net (code "87") (name "unconnected-(IC1-3V3-Pad41)") (class "Default")
      (node (ref "IC1") (pin "41") (pinfunction "3V3_41") (pintype "unspecified+no_connect"))
    )
    (net (code "88") (name "unconnected-(IC1-GND-Pad44)") (class "Default")
      (node (ref "IC1") (pin "44") (pinfunction "GND_44") (pintype "unspecified+no_connect"))
    )
    (net (code "89") (name "unconnected-(IC1-GP0-Pad1)") (class "Default")
      (node (ref "IC1") (pin "1") (pinfunction "GP0_1") (pintype "unspecified+no_connect"))
    )
    (net (code "90") (name "unconnected-(IC1-GP1-Pad2)") (class "Default")
      (node (ref "IC1") (pin "2") (pinfunction "GP1_2") (pintype "unspecified+no_connect"))
    )
    (net (code "91") (name "unconnected-(IC1-GP2-Pad4)") (class "Default")
      (node (ref "IC1") (pin "4") (pinfunction "GP2_4") (pintype "unspecified+no_connect"))
    )
    (net (code "92") (name "unconnected-(IC1-GP13-Pad17)") (class "Default")
      (node (ref "IC1") (pin "17") (pinfunction "GP13_17") (pintype "unspecified+no_connect"))
    )
    (net (code "93") (name "unconnected-(IC1-GP14-Pad19)") (class "Default")
      (node (ref "IC1") (pin "19") (pinfunction "GP14_19") (pintype "unspecified+no_connect"))
    )
    (net (code "94") (name "unconnected-(IC1-GP15-Pad20)") (class "Default")
      (node (ref "IC1") (pin "20") (pinfunction "GP15_20") (pintype "unspecified+no_connect"))
    )
    (net (code "95") (name "unconnected-(IC1-GP16-Pad21)") (class "Default")
      (node (ref "IC1") (pin "21") (pinfunction "GP16_21") (pintype "unspecified+no_connect"))
    )
    (net (code "96") (name "unconnected-(IC1-GP17-Pad22)") (class "Default")
      (node (ref "IC1") (pin "22") (pinfunction "GP17_22") (pintype "unspecified+no_connect"))
    )
    (net (code "97") (name "unconnected-(IC1-GP18-Pad24)") (class "Default")
      (node (ref "IC1") (pin "24") (pinfunction "GP18_24") (pintype "unspecified+no_connect"))
    )
    (net (code "98") (name "unconnected-(IC1-GP19-Pad25)") (class "Default")
      (node (ref "IC1") (pin "25") (pinfunction "GP19_25") (pintype "unspecified+no_connect"))
    )
    (net (code "99") (name "unconnected-(IC1-GP20-Pad26)") (class "Default")
      (node (ref "IC1") (pin "26") (pinfunction "GP20_26") (pintype "unspecified+no_connect"))
    )
    (net (code "100") (name "unconnected-(IC1-GP21-Pad27)") (class "Default")
      (node (ref "IC1") (pin "27") (pinfunction "GP21_27") (pintype "unspecified+no_connect"))
    )
    (net (code "101") (name "unconnected-(IC1-GP22-Pad29)") (class "Default")
      (node (ref "IC1") (pin "29") (pinfunction "GP22_29") (pintype "unspecified+no_connect"))
    )
    (net (code "102") (name "unconnected-(IC1-GP23-Pad37)") (class "Default")
      (node (ref "IC1") (pin "37") (pinfunction "GP23_37") (pintype "unspecified+no_connect"))
    )
    (net (code "103") (name "unconnected-(IC1-GP26-Pad31)") (class "Default")
      (node (ref "IC1") (pin "31") (pinfunction "GP26_31") (pintype "unspecified+no_connect"))
    )
    (net (code "104") (name "unconnected-(IC1-GP27-Pad32)") (class "Default")
      (node (ref "IC1") (pin "32") (pinfunction "GP27_32") (pintype "unspecified+no_connect"))
    )
    (net (code "105") (name "unconnected-(IC1-GP28-Pad34)") (class "Default")
      (node (ref "IC1") (pin "34") (pinfunction "GP28_34") (pintype "unspecified+no_connect"))
    )
    (net (code "106") (name "unconnected-(IC1-GP29-Pad35)") (class "Default")
      (node (ref "IC1") (pin "35") (pinfunction "GP29_35") (pintype "unspecified+no_connect"))
    )
    (net (code "107") (name "unconnected-(IC1-RUN-Pad30)") (class "Default")
      (node (ref "IC1") (pin "30") (pinfunction "RUN_30") (pintype "unspecified+no_connect"))
    )
    (net (code "108") (name "unconnected-(IC1-SWDCLK-Pad43)") (class "Default")
      (node (ref "IC1") (pin "43") (pinfunction "SWDCLK_43") (pintype "unspecified+no_connect"))
    )
    (net (code "109") (name "unconnected-(IC1-SWDIO-Pad42)") (class "Default")
      (node (ref "IC1") (pin "42") (pinfunction "SWDIO_42") (pintype "unspecified+no_connect"))
    )
    (net (code "110") (name "unconnected-(IC1-Vout-Pad40)") (class "Default")
      (node (ref "IC1") (pin "40") (pinfunction "Vout_40") (pintype "unspecified+no_connect"))
    )
    (net (code "111") (name "unconnected-(U1-DO-Pad4)") (class "Default")
      (node (ref "U1") (pin "4") (pinfunction "DO_4") (pintype "unspecified+no_connect"))
    )
    (net (code "112") (name "unconnected-(U22-SSTXP1-PadA2)") (class "Default")
      (node (ref "U22") (pin "A2") (pinfunction "SSTXP1_A2") (pintype "unspecified+no_connect"))
    )
    (net (code "113") (name "unconnected-(U22-SSTXp2-PadB2)") (class "Default")
      (node (ref "U22") (pin "B2") (pinfunction "SSTXp2_B2") (pintype "unspecified+no_connect"))
    )
    (net (code "114") (name "unconnected-(U42-GA5-Pad23)") (class "Default")
      (node (ref "U42") (pin "23") (pinfunction "GA5_23") (pintype "unspecified"))
    )
    (net (code "115") (name "unconnected-(U42-GA6-Pad22)") (class "Default")
      (node (ref "U42") (pin "22") (pinfunction "GA6_22") (pintype "unspecified"))
    )
    (net (code "116") (name "unconnected-(U42-GA7-Pad21)") (class "Default")
      (node (ref "U42") (pin "21") (pinfunction "GA7_21") (pintype "unspecified"))
    )
    (net (code "117") (name "unconnected-(U42-GB0-Pad1)") (class "Default")
      (node (ref "U42") (pin "1") (pinfunction "GB0_1") (pintype "unspecified"))
    )
    (net (code "118") (name "unconnected-(U42-GB1-Pad2)") (class "Default")
      (node (ref "U42") (pin "2") (pinfunction "GB1_2") (pintype "unspecified"))
    )
    (net (code "119") (name "unconnected-(U42-GB2-Pad3)") (class "Default")
      (node (ref "U42") (pin "3") (pinfunction "GB2_3") (pintype "unspecified"))
    )
    (net (code "120") (name "unconnected-(U42-GB3-Pad4)") (class "Default")
      (node (ref "U42") (pin "4") (pinfunction "GB3_4") (pintype "unspecified"))
    )
    (net (code "121") (name "unconnected-(U42-GB4-Pad5)") (class "Default")
      (node (ref "U42") (pin "5") (pinfunction "GB4_5") (pintype "unspecified"))
    )
    (net (code "122") (name "unconnected-(U42-GB5-Pad6)") (class "Default")
      (node (ref "U42") (pin "6") (pinfunction "GB5_6") (pintype "unspecified"))
    )
    (net (code "123") (name "unconnected-(U42-GB6-Pad7)") (class "Default")
      (node (ref "U42") (pin "7") (pinfunction "GB6_7") (pintype "unspecified"))
    )
    (net (code "124") (name "unconnected-(U42-GB7-Pad8)") (class "Default")
      (node (ref "U42") (pin "8") (pinfunction "GB7_8") (pintype "unspecified"))
    )
    (net (code "125") (name "unconnected-(U42-INTa-Pad20)") (class "Default")
      (node (ref "U42") (pin "20") (pinfunction "INTa_20") (pintype "unspecified+no_connect"))
    )
    (net (code "126") (name "unconnected-(U42-INTb-Pad19)") (class "Default")
      (node (ref "U42") (pin "19") (pinfunction "INTb_19") (pintype "unspecified+no_connect"))
    )
    (net (code "127") (name "unconnected-(U42-NC-Pad11)") (class "Default")
      (node (ref "U42") (pin "11") (pinfunction "NC_11") (pintype "unspecified+no_connect"))
    )
    (net (code "128") (name "unconnected-(U42-NC-Pad14)") (class "Default")
      (node (ref "U42") (pin "14") (pinfunction "NC_14") (pintype "unspecified+no_connect"))
    )
    (net (code "129") (name "unconnected-(U42-^RST-Pad18)") (class "Default")
      (node (ref "U42") (pin "18") (pinfunction "^RST_18") (pintype "unspecified+no_connect"))
    )
    (net (code "130") (name "unconnected-(U81-INTa-Pad20)") (class "Default")
      (node (ref "U81") (pin "20") (pinfunction "INTa_20") (pintype "unspecified+no_connect"))
    )
    (net (code "131") (name "unconnected-(U81-INTb-Pad19)") (class "Default")
      (node (ref "U81") (pin "19") (pinfunction "INTb_19") (pintype "unspecified+no_connect"))
    )
    (net (code "132") (name "unconnected-(U81-NC-Pad11)") (class "Default")
      (node (ref "U81") (pin "11") (pinfunction "NC_11") (pintype "unspecified+no_connect"))
    )
    (net (code "133") (name "unconnected-(U81-NC-Pad14)") (class "Default")
      (node (ref "U81") (pin "14") (pinfunction "NC_14") (pintype "unspecified+no_connect"))
    )
    (net (code "134") (name "unconnected-(U81-^RST-Pad18)") (class "Default")
      (node (ref "U81") (pin "18") (pinfunction "^RST_18") (pintype "unspecified+no_connect"))
    )
    (net (code "135") (name "unconnected-(U82-INTa-Pad20)") (class "Default")
      (node (ref "U82") (pin "20") (pinfunction "INTa_20") (pintype "unspecified+no_connect"))
    )
    (net (code "136") (name "unconnected-(U82-INTb-Pad19)") (class "Default")
      (node (ref "U82") (pin "19") (pinfunction "INTb_19") (pintype "unspecified+no_connect"))
    )
    (net (code "137") (name "unconnected-(U82-NC-Pad11)") (class "Default")
      (node (ref "U82") (pin "11") (pinfunction "NC_11") (pintype "unspecified+no_connect"))
    )
    (net (code "138") (name "unconnected-(U82-NC-Pad14)") (class "Default")
      (node (ref "U82") (pin "14") (pinfunction "NC_14") (pintype "unspecified+no_connect"))
    )
    (net (code "139") (name "unconnected-(U82-^RST-Pad18)") (class "Default")
      (node (ref "U82") (pin "18") (pinfunction "^RST_18") (pintype "unspecified+no_connect"))
    )
  )
)
